# CLKB_temp_sensors.net
KiCad netlist of a schematic drawn in Altium Designer
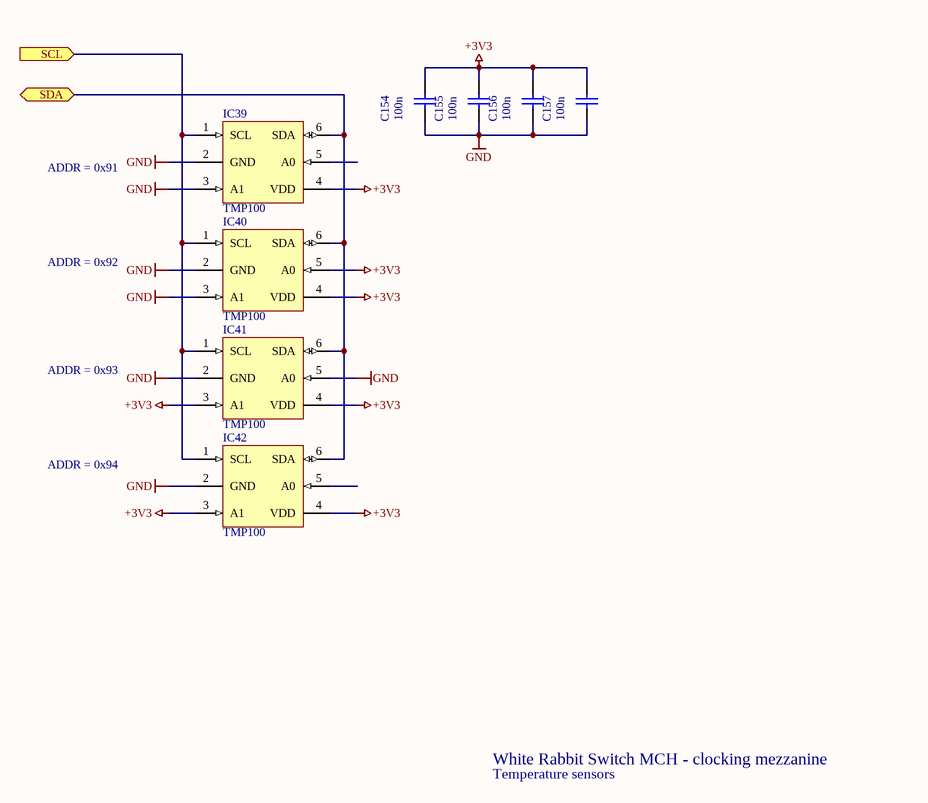
[diagram p0: CLKB_temp_sensors.SchDoc]

(export (version "E")
  (design (tool "Eeschema 10.0.6"))
  (components
    (comp (ref "C154")
      (value "100n")
      (footprint "CAPC1608X87N")
      (description "Non-polarised capacitor")
      (fields
        (field (name "PART NUMBER") "CC0603_100NF_50V_10%_X7R")
        (field (name "VOLTAGE") "50V")
        (field (name "AUTHOR") "CERN DEM JLC")
      )
      (libsource (lib "Capacitors") (part "Capacitor - non polarized"))
    )
    (comp (ref "C155")
      (value "100n")
      (footprint "CAPC1608X87N")
      (description "Non-polarised capacitor")
      (fields
        (field (name "PART NUMBER") "CC0603_100NF_50V_10%_X7R")
        (field (name "VOLTAGE") "50V")
        (field (name "AUTHOR") "CERN DEM JLC")
      )
      (libsource (lib "Capacitors") (part "Capacitor - non polarized"))
    )
    (comp (ref "C156")
      (value "100n")
      (footprint "CAPC1608X87N")
      (description "Non-polarised capacitor")
      (fields
        (field (name "PART NUMBER") "CC0603_100NF_50V_10%_X7R")
        (field (name "VOLTAGE") "50V")
        (field (name "AUTHOR") "CERN DEM JLC")
      )
      (libsource (lib "Capacitors") (part "Capacitor - non polarized"))
    )
    (comp (ref "C157")
      (value "100n")
      (footprint "CAPC1608X87N")
      (description "Non-polarised capacitor")
      (fields
        (field (name "PART NUMBER") "CC0603_100NF_50V_10%_X7R")
        (field (name "VOLTAGE") "50V")
        (field (name "AUTHOR") "CERN DEM JLC")
      )
      (libsource (lib "Capacitors") (part "Capacitor - non polarized"))
    )
    (comp (ref "IC39")
      (value "TMP100")
      (footprint "SOT23A-6L")
      (description "I2C temp. sensor")
      (libsource (lib "wr_switch") (part "TMP100"))
    )
    (comp (ref "IC40")
      (value "TMP100")
      (footprint "SOT23A-6L")
      (description "I2C temp. sensor")
      (libsource (lib "wr_switch") (part "TMP100"))
    )
    (comp (ref "IC41")
      (value "TMP100")
      (footprint "SOT23A-6L")
      (description "I2C temp. sensor")
      (libsource (lib "wr_switch") (part "TMP100"))
    )
    (comp (ref "IC42")
      (value "TMP100")
      (footprint "SOT23A-6L")
      (description "I2C temp. sensor")
      (libsource (lib "wr_switch") (part "TMP100"))
    )
  )
  (nets
    (net (code "1") (name "+3V3") (class "Default")
      (node (ref "C154") (pin "2") (pinfunction "2_2") (pintype "passive"))
      (node (ref "C155") (pin "2") (pinfunction "2_2") (pintype "passive"))
      (node (ref "C156") (pin "2") (pinfunction "2_2") (pintype "passive"))
      (node (ref "C157") (pin "2") (pinfunction "2_2") (pintype "passive"))
      (node (ref "IC39") (pin "4") (pinfunction "VDD_4") (pintype "power_in"))
      (node (ref "IC40") (pin "4") (pinfunction "VDD_4") (pintype "power_in"))
      (node (ref "IC40") (pin "5") (pinfunction "A0_5") (pintype "input"))
      (node (ref "IC41") (pin "3") (pinfunction "A1_3") (pintype "input"))
      (node (ref "IC41") (pin "4") (pinfunction "VDD_4") (pintype "power_in"))
      (node (ref "IC42") (pin "3") (pinfunction "A1_3") (pintype "input"))
      (node (ref "IC42") (pin "4") (pinfunction "VDD_4") (pintype "power_in"))
    )
    (net (code "2") (name "/SCL") (class "Default")
      (node (ref "IC39") (pin "1") (pinfunction "SCL_1") (pintype "input"))
      (node (ref "IC40") (pin "1") (pinfunction "SCL_1") (pintype "input"))
      (node (ref "IC41") (pin "1") (pinfunction "SCL_1") (pintype "input"))
      (node (ref "IC42") (pin "1") (pinfunction "SCL_1") (pintype "input"))
    )
    (net (code "3") (name "/SDA") (class "Default")
      (node (ref "IC39") (pin "6") (pinfunction "SDA_6") (pintype "bidirectional"))
      (node (ref "IC40") (pin "6") (pinfunction "SDA_6") (pintype "bidirectional"))
      (node (ref "IC41") (pin "6") (pinfunction "SDA_6") (pintype "bidirectional"))
      (node (ref "IC42") (pin "6") (pinfunction "SDA_6") (pintype "bidirectional"))
    )
    (net (code "4") (name "GND") (class "Default")
      (node (ref "C154") (pin "1") (pinfunction "1_1") (pintype "passive"))
      (node (ref "C155") (pin "1") (pinfunction "1_1") (pintype "passive"))
      (node (ref "C156") (pin "1") (pinfunction "1_1") (pintype "passive"))
      (node (ref "C157") (pin "1") (pinfunction "1_1") (pintype "passive"))
      (node (ref "IC39") (pin "2") (pinfunction "GND_2") (pintype "power_in"))
      (node (ref "IC39") (pin "3") (pinfunction "A1_3") (pintype "input"))
      (node (ref "IC40") (pin "2") (pinfunction "GND_2") (pintype "power_in"))
      (node (ref "IC40") (pin "3") (pinfunction "A1_3") (pintype "input"))
      (node (ref "IC41") (pin "2") (pinfunction "GND_2") (pintype "power_in"))
      (node (ref "IC41") (pin "5") (pinfunction "A0_5") (pintype "input"))
      (node (ref "IC42") (pin "2") (pinfunction "GND_2") (pintype "power_in"))
    )
    (net (code "5") (name "unconnected-(IC39-A0-Pad5)") (class "Default")
      (node (ref "IC39") (pin "5") (pinfunction "A0_5") (pintype "input"))
    )
    (net (code "6") (name "unconnected-(IC42-A0-Pad5)") (class "Default")
      (node (ref "IC42") (pin "5") (pinfunction "A0_5") (pintype "input"))
    )
  )
)
